# Sheet1.net
KiCad netlist of a schematic drawn in Altium Designer
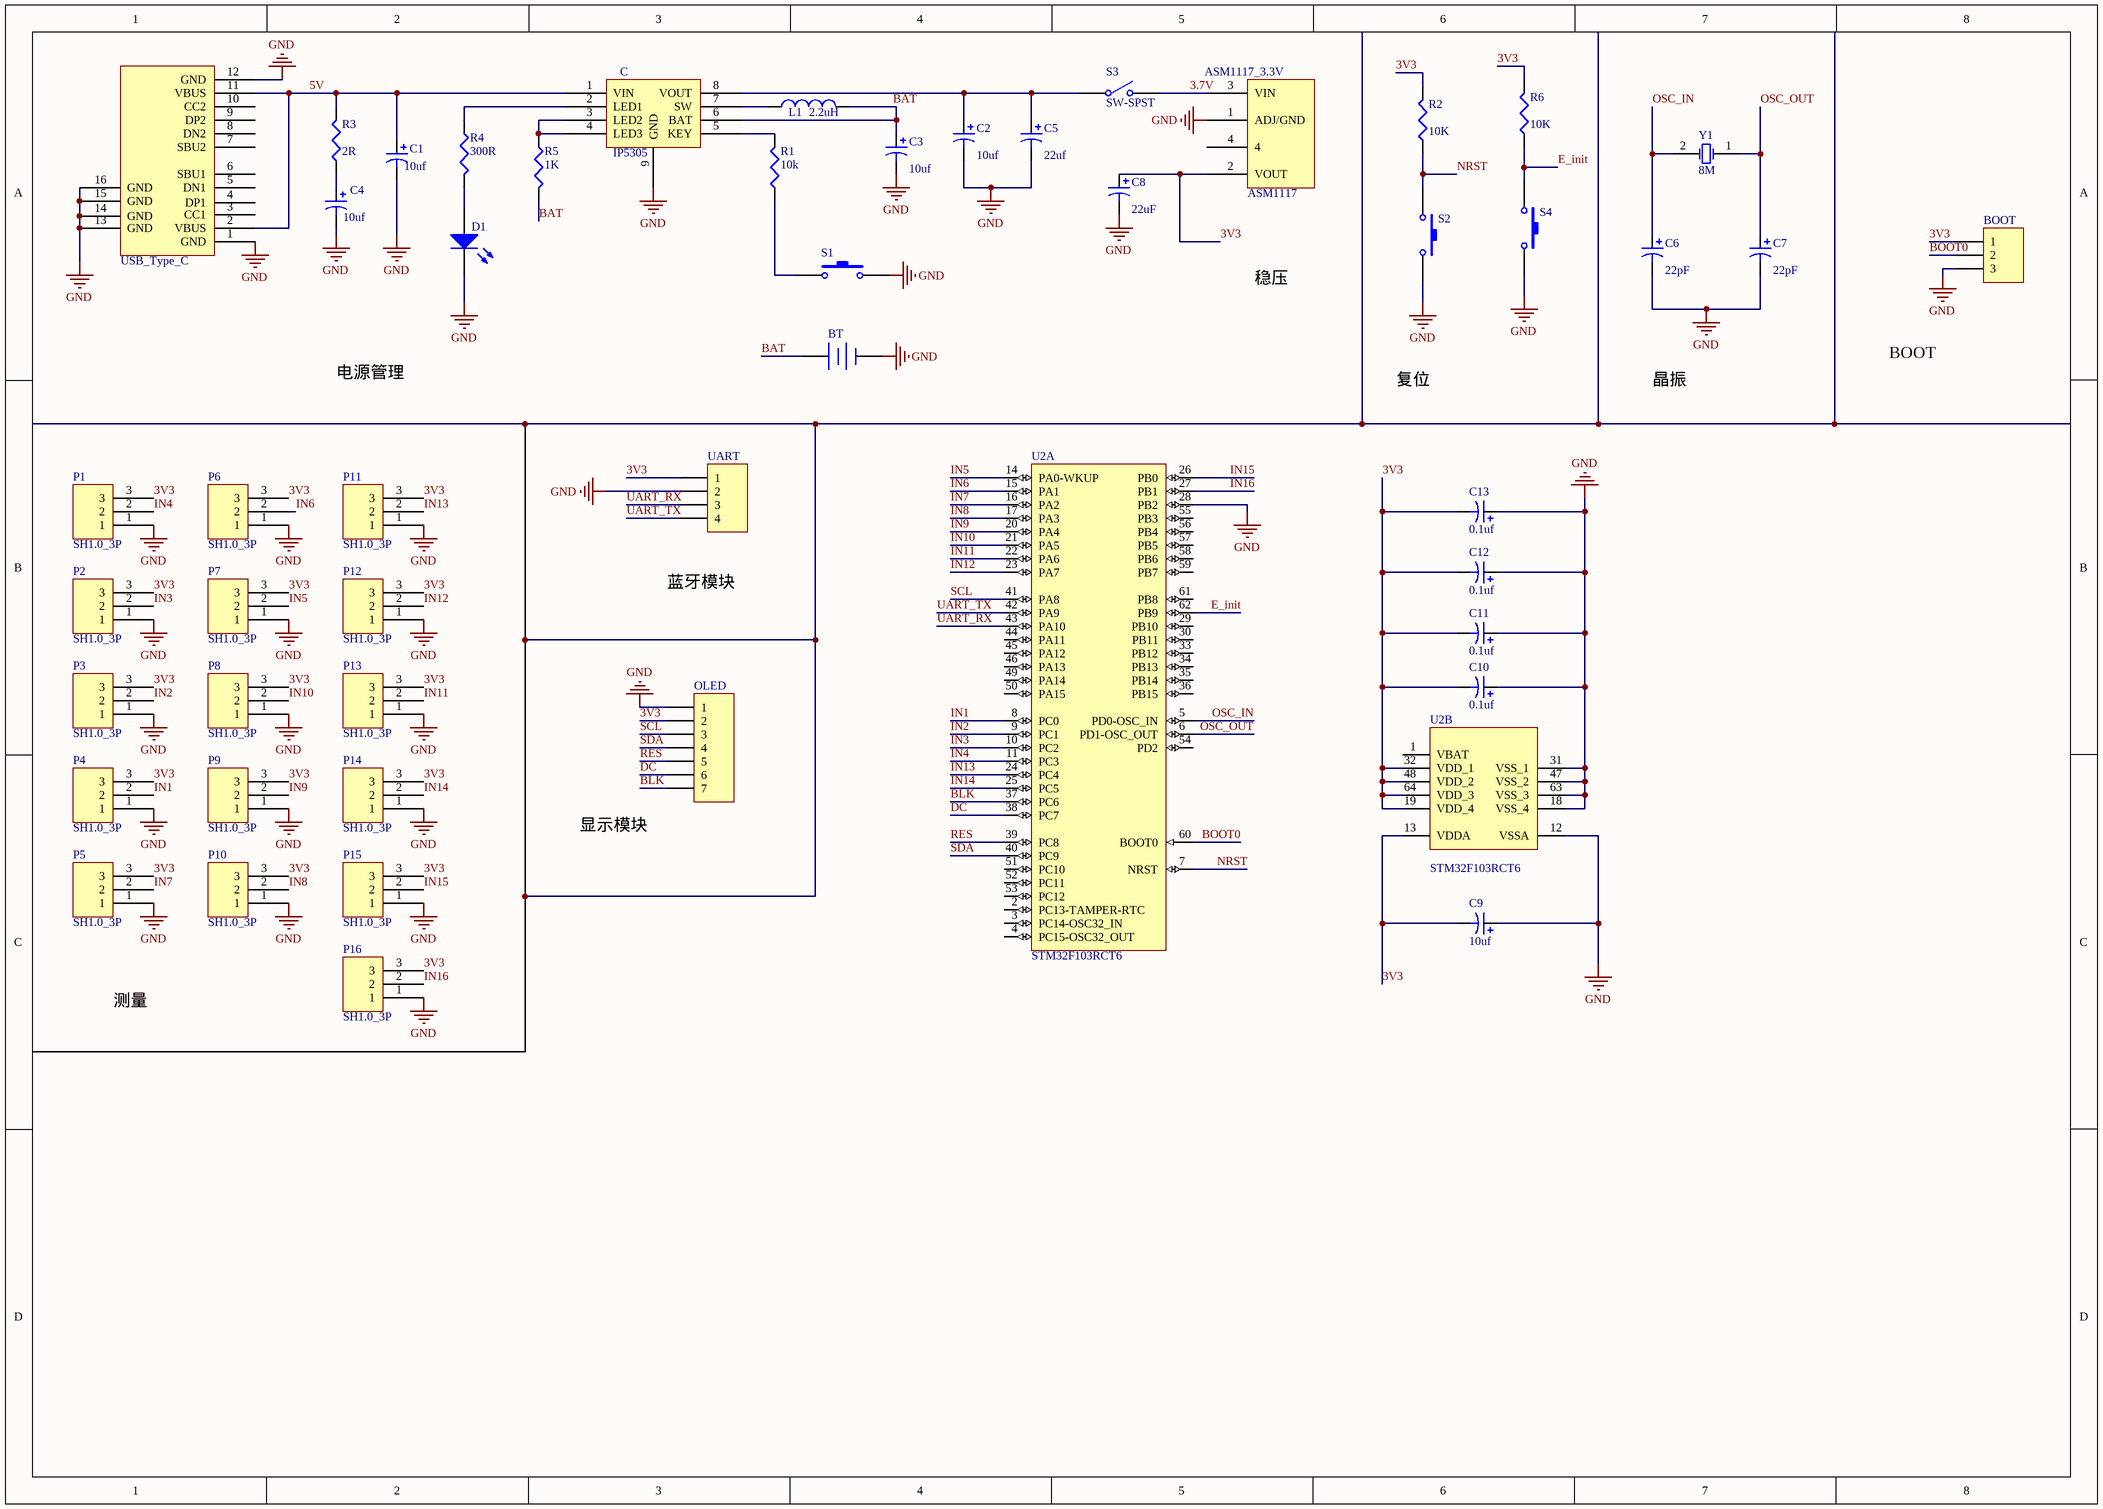
[diagram p0: Sheet1.SchDoc]

(export (version "E")
  (design (tool "Eeschema 10.0.6"))
  (components
    (comp (ref "*")
      (value "USB_Type_C")
      (footprint "USB_Type_C")
      (libsource (lib "Schlib1") (part "USB_Type_C"))
    )
    (comp (ref "ASM1117")
      (value "ASM1117_3.3V")
      (footprint "SOT223_N")
      (libsource (lib "Schlib1") (part "ASM1117_3.3V"))
    )
    (comp (ref "BOOT")
      (value "Header 3")
      (footprint "HDR1X3")
      (description "Header, 3-Pin")
      (fields (field (name "PUBLISHER") "Altium Limited"))
      (libsource (lib "Miscellaneous Connectors") (part "Header 3"))
    )
    (comp (ref "BT")
      (value "Battery")
      (footprint "BAT-2")
      (description "Multicell Battery")
      (fields (field (name "PUBLISHER") "Altium Limited"))
      (libsource (lib "Miscellaneous Devices") (part "Battery"))
    )
    (comp (ref "C") (value "IP5305") (footprint "SOP8_1") (libsource (lib "Schlib1") (part "IP5305")))
    (comp (ref "C1")
      (value "10uf")
      (footprint "J1-0603")
      (description "Polarized Capacitor (Surface Mount)")
      (fields (field (name "Comment") "Cap Pol3") (field (name "PUBLISHER") "Altium Limited"))
      (libsource (lib "Miscellaneous Devices") (part "Cap Pol3"))
    )
    (comp (ref "C2")
      (value "10uf")
      (footprint "J1-0603")
      (description "Polarized Capacitor (Surface Mount)")
      (fields (field (name "Comment") "Cap Pol3") (field (name "PUBLISHER") "Altium Limited"))
      (libsource (lib "Miscellaneous Devices") (part "Cap Pol3"))
    )
    (comp (ref "C3")
      (value "10uf")
      (footprint "J1-0603")
      (description "Polarized Capacitor (Surface Mount)")
      (fields (field (name "Comment") "Cap Pol3") (field (name "PUBLISHER") "Altium Limited"))
      (libsource (lib "Miscellaneous Devices") (part "Cap Pol3"))
    )
    (comp (ref "C4")
      (value "10uf")
      (footprint "J1-0603")
      (description "Polarized Capacitor (Surface Mount)")
      (fields (field (name "Comment") "Cap Pol3") (field (name "PUBLISHER") "Altium Limited"))
      (libsource (lib "Miscellaneous Devices") (part "Cap Pol3"))
    )
    (comp (ref "C5")
      (value "22uf")
      (footprint "J1-0603")
      (description "Polarized Capacitor (Surface Mount)")
      (fields (field (name "Comment") "Cap Pol3") (field (name "PUBLISHER") "Altium Limited"))
      (libsource (lib "Miscellaneous Devices") (part "Cap Pol3"))
    )
    (comp (ref "C6")
      (value "22pF")
      (footprint "J1-0603")
      (description "Polarized Capacitor (Surface Mount)")
      (fields (field (name "Comment") "Cap Pol3") (field (name "PUBLISHER") "Altium Limited"))
      (libsource (lib "Miscellaneous Devices") (part "Cap Pol3"))
    )
    (comp (ref "C7")
      (value "22pF")
      (footprint "J1-0603")
      (description "Polarized Capacitor (Surface Mount)")
      (fields (field (name "Comment") "Cap Pol3") (field (name "PUBLISHER") "Altium Limited"))
      (libsource (lib "Miscellaneous Devices") (part "Cap Pol3"))
    )
    (comp (ref "C8")
      (value "22uF")
      (footprint "J1-0603")
      (description "Polarized Capacitor (Surface Mount)")
      (fields (field (name "Comment") "Cap Pol3") (field (name "PUBLISHER") "Altium Limited"))
      (libsource (lib "Miscellaneous Devices") (part "Cap Pol3"))
    )
    (comp (ref "C9")
      (value "10uf")
      (footprint "J1-0603")
      (description "Polarized Capacitor (Surface Mount)")
      (fields (field (name "Comment") "Cap Pol3") (field (name "PUBLISHER") "Altium Limited"))
      (libsource (lib "Miscellaneous Devices") (part "Cap Pol3"))
    )
    (comp (ref "C10")
      (value "0.1uf")
      (footprint "J1-0603")
      (description "Polarized Capacitor (Surface Mount)")
      (fields (field (name "Comment") "Cap Pol3") (field (name "PUBLISHER") "Altium Limited"))
      (libsource (lib "Miscellaneous Devices") (part "Cap Pol3"))
    )
    (comp (ref "C11")
      (value "0.1uf")
      (footprint "J1-0603")
      (description "Polarized Capacitor (Surface Mount)")
      (fields (field (name "Comment") "Cap Pol3") (field (name "PUBLISHER") "Altium Limited"))
      (libsource (lib "Miscellaneous Devices") (part "Cap Pol3"))
    )
    (comp (ref "C12")
      (value "0.1uf")
      (footprint "J1-0603")
      (description "Polarized Capacitor (Surface Mount)")
      (fields (field (name "Comment") "Cap Pol3") (field (name "PUBLISHER") "Altium Limited"))
      (libsource (lib "Miscellaneous Devices") (part "Cap Pol3"))
    )
    (comp (ref "C13")
      (value "0.1uf")
      (footprint "J1-0603")
      (description "Polarized Capacitor (Surface Mount)")
      (fields (field (name "Comment") "Cap Pol3") (field (name "PUBLISHER") "Altium Limited"))
      (libsource (lib "Miscellaneous Devices") (part "Cap Pol3"))
    )
    (comp (ref "D1")
      (value "LED2")
      (footprint "J1-0603")
      (description "Typical RED, GREEN, YELLOW, AMBER GaAs LED")
      (fields (field (name "PUBLISHER") "Altium Limited"))
      (libsource (lib "Miscellaneous Devices") (part "LED2"))
    )
    (comp (ref "L1")
      (value "2.2uH")
      (footprint "CD43")
      (description "Inductor")
      (fields (field (name "PUBLISHER") "Altium Limited"))
      (libsource (lib "Miscellaneous Devices") (part "Inductor"))
    )
    (comp (ref "OLED")
      (value "MHDR1X7")
      (footprint "HDR1X7")
      (description "Header, 7-Pin")
      (fields (field (name "PUBLISHER") "Altium Limited"))
      (libsource (lib "Miscellaneous Connectors") (part "MHDR1X7"))
    )
    (comp (ref "P1") (value "SH1.0_3P") (footprint "SH1_3P_2") (libsource (lib "Schlib1") (part "SH1.0_3P")))
    (comp (ref "P2") (value "SH1.0_3P") (footprint "SH1_3P_2") (libsource (lib "Schlib1") (part "SH1.0_3P")))
    (comp (ref "P3") (value "SH1.0_3P") (footprint "SH1_3P_2") (libsource (lib "Schlib1") (part "SH1.0_3P")))
    (comp (ref "P4") (value "SH1.0_3P") (footprint "SH1_3P_2") (libsource (lib "Schlib1") (part "SH1.0_3P")))
    (comp (ref "P5") (value "SH1.0_3P") (footprint "SH1_3P_2") (libsource (lib "Schlib1") (part "SH1.0_3P")))
    (comp (ref "P6") (value "SH1.0_3P") (footprint "SH1_3P_2") (libsource (lib "Schlib1") (part "SH1.0_3P")))
    (comp (ref "P7") (value "SH1.0_3P") (footprint "SH1_3P_2") (libsource (lib "Schlib1") (part "SH1.0_3P")))
    (comp (ref "P8") (value "SH1.0_3P") (footprint "SH1_3P_2") (libsource (lib "Schlib1") (part "SH1.0_3P")))
    (comp (ref "P9") (value "SH1.0_3P") (footprint "SH1_3P_2") (libsource (lib "Schlib1") (part "SH1.0_3P")))
    (comp (ref "P10") (value "SH1.0_3P") (footprint "SH1_3P_2") (libsource (lib "Schlib1") (part "SH1.0_3P")))
    (comp (ref "P11") (value "SH1.0_3P") (footprint "SH1_3P_2") (libsource (lib "Schlib1") (part "SH1.0_3P")))
    (comp (ref "P12") (value "SH1.0_3P") (footprint "SH1_3P_2") (libsource (lib "Schlib1") (part "SH1.0_3P")))
    (comp (ref "P13") (value "SH1.0_3P") (footprint "SH1_3P_2") (libsource (lib "Schlib1") (part "SH1.0_3P")))
    (comp (ref "P14") (value "SH1.0_3P") (footprint "SH1_3P_2") (libsource (lib "Schlib1") (part "SH1.0_3P")))
    (comp (ref "P15") (value "SH1.0_3P") (footprint "SH1_3P_2") (libsource (lib "Schlib1") (part "SH1.0_3P")))
    (comp (ref "P16") (value "SH1.0_3P") (footprint "SH1_3P_2") (libsource (lib "Schlib1") (part "SH1.0_3P")))
    (comp (ref "R1")
      (value "10k")
      (footprint "J1-0603")
      (description "Resistor")
      (fields (field (name "Comment") "Res3") (field (name "PUBLISHER") "Altium Limited"))
      (libsource (lib "Miscellaneous Devices") (part "Res3"))
    )
    (comp (ref "R2")
      (value "10K")
      (footprint "J1-0603")
      (description "Resistor")
      (fields (field (name "Comment") "Res3") (field (name "PUBLISHER") "Altium Limited"))
      (libsource (lib "Miscellaneous Devices") (part "Res3"))
    )
    (comp (ref "R3")
      (value "2R")
      (footprint "J1-0603")
      (description "Resistor")
      (fields (field (name "Comment") "Res3") (field (name "PUBLISHER") "Altium Limited"))
      (libsource (lib "Miscellaneous Devices") (part "Res3"))
    )
    (comp (ref "R4")
      (value "300R")
      (footprint "J1-0603")
      (description "Resistor")
      (fields (field (name "Comment") "Res3") (field (name "PUBLISHER") "Altium Limited"))
      (libsource (lib "Miscellaneous Devices") (part "Res3"))
    )
    (comp (ref "R5")
      (value "1K")
      (footprint "J1-0603")
      (description "Resistor")
      (fields (field (name "Comment") "Res3") (field (name "PUBLISHER") "Altium Limited"))
      (libsource (lib "Miscellaneous Devices") (part "Res3"))
    )
    (comp (ref "R6")
      (value "10K")
      (footprint "J1-0603")
      (description "Resistor")
      (fields (field (name "Comment") "Res3") (field (name "PUBLISHER") "Altium Limited"))
      (libsource (lib "Miscellaneous Devices") (part "Res3"))
    )
    (comp (ref "S1")
      (value "SW-PB")
      (footprint "SW_DP_1")
      (description "Switch")
      (fields (field (name "PUBLISHER") "Altium Limited"))
      (libsource (lib "Miscellaneous Devices") (part "SW-PB"))
    )
    (comp (ref "S2")
      (value "SW-PB")
      (footprint "SW_DP_1")
      (description "Switch")
      (fields (field (name "PUBLISHER") "Altium Limited"))
      (libsource (lib "Miscellaneous Devices") (part "SW-PB"))
    )
    (comp (ref "S3")
      (value "SW-SPST")
      (footprint "SW_s1")
      (description "Single-Pole, Single-Throw Switch")
      (fields (field (name "PUBLISHER") "Altium Limited"))
      (libsource (lib "Miscellaneous Devices") (part "SW-SPST"))
    )
    (comp (ref "S4")
      (value "SW-PB")
      (footprint "SW_DP_1")
      (description "Switch")
      (fields (field (name "PUBLISHER") "Altium Limited"))
      (libsource (lib "Miscellaneous Devices") (part "SW-PB"))
    )
    (comp (ref "U2")
      (value "STM32F103RCT6")
      (footprint "STM-LQFP64_N")
      (libsource (lib "") (part "STM32F103RCT6_1"))
    )
    (comp (ref "UART")
      (value "Header 4")
      (footprint "HDR1X4")
      (description "Header, 4-Pin")
      (fields (field (name "PUBLISHER") "Altium Limited"))
      (libsource (lib "Miscellaneous Connectors") (part "Header 4"))
    )
    (comp (ref "Y1")
      (value "8M")
      (footprint "YXC_8M")
      (description "Crystal Oscillator")
      (fields (field (name "PUBLISHER") "Altium Limited"))
      (libsource (lib "Miscellaneous Devices") (part "XTAL"))
    )
  )
  (nets
    (net (code "1") (name "/3.7V") (class "Default")
      (node (ref "ASM1117") (pin "3") (pinfunction "VIN_3") (pintype "passive"))
      (node (ref "S3") (pin "2") (pinfunction "NO_2") (pintype "passive"))
    )
    (net (code "2") (name "/3V3") (class "Default")
      (node (ref "ASM1117") (pin "2") (pinfunction "VOUT_2") (pintype "passive"))
      (node (ref "BOOT") (pin "1") (pinfunction "1_1") (pintype "passive"))
      (node (ref "C10") (pin "2") (pinfunction "2_2") (pintype "passive"))
      (node (ref "C11") (pin "2") (pinfunction "2_2") (pintype "passive"))
      (node (ref "C12") (pin "2") (pinfunction "2_2") (pintype "passive"))
      (node (ref "C13") (pin "2") (pinfunction "2_2") (pintype "passive"))
      (node (ref "C8") (pin "1") (pinfunction "1_1") (pintype "passive"))
      (node (ref "C9") (pin "2") (pinfunction "2_2") (pintype "passive"))
      (node (ref "OLED") (pin "2") (pinfunction "2_2") (pintype "passive"))
      (node (ref "P1") (pin "3") (pinfunction "3_3") (pintype "passive"))
      (node (ref "P10") (pin "3") (pinfunction "3_3") (pintype "passive"))
      (node (ref "P11") (pin "3") (pinfunction "3_3") (pintype "passive"))
      (node (ref "P12") (pin "3") (pinfunction "3_3") (pintype "passive"))
      (node (ref "P13") (pin "3") (pinfunction "3_3") (pintype "passive"))
      (node (ref "P14") (pin "3") (pinfunction "3_3") (pintype "passive"))
      (node (ref "P15") (pin "3") (pinfunction "3_3") (pintype "passive"))
      (node (ref "P16") (pin "3") (pinfunction "3_3") (pintype "passive"))
      (node (ref "P2") (pin "3") (pinfunction "3_3") (pintype "passive"))
      (node (ref "P3") (pin "3") (pinfunction "3_3") (pintype "passive"))
      (node (ref "P4") (pin "3") (pinfunction "3_3") (pintype "passive"))
      (node (ref "P5") (pin "3") (pinfunction "3_3") (pintype "passive"))
      (node (ref "P6") (pin "3") (pinfunction "3_3") (pintype "passive"))
      (node (ref "P7") (pin "3") (pinfunction "3_3") (pintype "passive"))
      (node (ref "P8") (pin "3") (pinfunction "3_3") (pintype "passive"))
      (node (ref "P9") (pin "3") (pinfunction "3_3") (pintype "passive"))
      (node (ref "R2") (pin "2") (pinfunction "2_2") (pintype "passive"))
      (node (ref "R6") (pin "2") (pinfunction "2_2") (pintype "passive"))
      (node (ref "U2") (pin "13") (pinfunction "VDDA_13") (pintype "power_in"))
      (node (ref "U2") (pin "19") (pinfunction "VDD_4_19") (pintype "power_in"))
      (node (ref "U2") (pin "32") (pinfunction "VDD_1_32") (pintype "power_in"))
      (node (ref "U2") (pin "48") (pinfunction "VDD_2_48") (pintype "power_in"))
      (node (ref "U2") (pin "64") (pinfunction "VDD_3_64") (pintype "power_in"))
      (node (ref "UART") (pin "1") (pinfunction "1_1") (pintype "passive"))
    )
    (net (code "3") (name "/5V") (class "Default")
      (node (ref "*") (pin "11") (pinfunction "VBUS_11") (pintype "passive"))
      (node (ref "*") (pin "2") (pinfunction "VBUS_2") (pintype "passive"))
      (node (ref "C") (pin "1") (pinfunction "VIN_1") (pintype "passive"))
      (node (ref "C1") (pin "1") (pinfunction "1_1") (pintype "passive"))
      (node (ref "R3") (pin "2") (pinfunction "2_2") (pintype "passive"))
    )
    (net (code "4") (name "/BAT") (class "Default")
      (node (ref "BT") (pin "1") (pinfunction "+_1") (pintype "passive"))
      (node (ref "C") (pin "6") (pinfunction "BAT_6") (pintype "passive"))
      (node (ref "C3") (pin "1") (pinfunction "1_1") (pintype "passive"))
      (node (ref "L1") (pin "2") (pinfunction "2_2") (pintype "passive"))
      (node (ref "R5") (pin "2") (pinfunction "2_2") (pintype "passive"))
    )
    (net (code "5") (name "/BLK") (class "Default")
      (node (ref "OLED") (pin "7") (pinfunction "7_7") (pintype "passive"))
      (node (ref "U2") (pin "37") (pinfunction "PC6_37") (pintype "bidirectional"))
    )
    (net (code "6") (name "/BOOT0") (class "Default")
      (node (ref "BOOT") (pin "2") (pinfunction "2_2") (pintype "passive"))
      (node (ref "U2") (pin "60") (pinfunction "BOOT0_60") (pintype "input"))
    )
    (net (code "7") (name "/DC") (class "Default")
      (node (ref "OLED") (pin "6") (pinfunction "6_6") (pintype "passive"))
      (node (ref "U2") (pin "38") (pinfunction "PC7_38") (pintype "bidirectional"))
    )
    (net (code "8") (name "/E_init") (class "Default")
      (node (ref "R6") (pin "1") (pinfunction "1_1") (pintype "passive"))
      (node (ref "S4") (pin "1") (pinfunction "1_1") (pintype "passive"))
      (node (ref "U2") (pin "62") (pinfunction "PB9_62") (pintype "bidirectional"))
    )
    (net (code "9") (name "/IN1") (class "Default")
      (node (ref "P4") (pin "2") (pinfunction "2_2") (pintype "passive"))
      (node (ref "U2") (pin "8") (pinfunction "PC0_8") (pintype "bidirectional"))
    )
    (net (code "10") (name "/IN2") (class "Default")
      (node (ref "P3") (pin "2") (pinfunction "2_2") (pintype "passive"))
      (node (ref "U2") (pin "9") (pinfunction "PC1_9") (pintype "bidirectional"))
    )
    (net (code "11") (name "/IN3") (class "Default")
      (node (ref "P2") (pin "2") (pinfunction "2_2") (pintype "passive"))
      (node (ref "U2") (pin "10") (pinfunction "PC2_10") (pintype "bidirectional"))
    )
    (net (code "12") (name "/IN4") (class "Default")
      (node (ref "P1") (pin "2") (pinfunction "2_2") (pintype "passive"))
      (node (ref "U2") (pin "11") (pinfunction "PC3_11") (pintype "bidirectional"))
    )
    (net (code "13") (name "/IN5") (class "Default")
      (node (ref "P7") (pin "2") (pinfunction "2_2") (pintype "passive"))
      (node (ref "U2") (pin "14") (pinfunction "PA0-WKUP_14") (pintype "bidirectional"))
    )
    (net (code "14") (name "/IN6") (class "Default")
      (node (ref "P6") (pin "2") (pinfunction "2_2") (pintype "passive"))
      (node (ref "U2") (pin "15") (pinfunction "PA1_15") (pintype "bidirectional"))
    )
    (net (code "15") (name "/IN7") (class "Default")
      (node (ref "P5") (pin "2") (pinfunction "2_2") (pintype "passive"))
      (node (ref "U2") (pin "16") (pinfunction "PA2_16") (pintype "bidirectional"))
    )
    (net (code "16") (name "/IN8") (class "Default")
      (node (ref "P10") (pin "2") (pinfunction "2_2") (pintype "passive"))
      (node (ref "U2") (pin "17") (pinfunction "PA3_17") (pintype "bidirectional"))
    )
    (net (code "17") (name "/IN9") (class "Default")
      (node (ref "P9") (pin "2") (pinfunction "2_2") (pintype "passive"))
      (node (ref "U2") (pin "20") (pinfunction "PA4_20") (pintype "bidirectional"))
    )
    (net (code "18") (name "/IN10") (class "Default")
      (node (ref "P8") (pin "2") (pinfunction "2_2") (pintype "passive"))
      (node (ref "U2") (pin "21") (pinfunction "PA5_21") (pintype "bidirectional"))
    )
    (net (code "19") (name "/IN11") (class "Default")
      (node (ref "P13") (pin "2") (pinfunction "2_2") (pintype "passive"))
      (node (ref "U2") (pin "22") (pinfunction "PA6_22") (pintype "bidirectional"))
    )
    (net (code "20") (name "/IN12") (class "Default")
      (node (ref "P12") (pin "2") (pinfunction "2_2") (pintype "passive"))
      (node (ref "U2") (pin "23") (pinfunction "PA7_23") (pintype "bidirectional"))
    )
    (net (code "21") (name "/IN13") (class "Default")
      (node (ref "P11") (pin "2") (pinfunction "2_2") (pintype "passive"))
      (node (ref "U2") (pin "24") (pinfunction "PC4_24") (pintype "bidirectional"))
    )
    (net (code "22") (name "/IN14") (class "Default")
      (node (ref "P14") (pin "2") (pinfunction "2_2") (pintype "passive"))
      (node (ref "U2") (pin "25") (pinfunction "PC5_25") (pintype "bidirectional"))
    )
    (net (code "23") (name "/IN15") (class "Default")
      (node (ref "P15") (pin "2") (pinfunction "2_2") (pintype "passive"))
      (node (ref "U2") (pin "26") (pinfunction "PB0_26") (pintype "bidirectional"))
    )
    (net (code "24") (name "/IN16") (class "Default")
      (node (ref "P16") (pin "2") (pinfunction "2_2") (pintype "passive"))
      (node (ref "U2") (pin "27") (pinfunction "PB1_27") (pintype "bidirectional"))
    )
    (net (code "25") (name "/NRST") (class "Default")
      (node (ref "R2") (pin "1") (pinfunction "1_1") (pintype "passive"))
      (node (ref "S2") (pin "1") (pinfunction "1_1") (pintype "passive"))
      (node (ref "U2") (pin "7") (pinfunction "NRST_7") (pintype "bidirectional"))
    )
    (net (code "26") (name "/OSC_IN") (class "Default")
      (node (ref "C6") (pin "1") (pinfunction "1_1") (pintype "passive"))
      (node (ref "U2") (pin "5") (pinfunction "PD0-OSC_IN_5") (pintype "bidirectional"))
      (node (ref "Y1") (pin "2") (pinfunction "OSC2_2") (pintype "passive"))
    )
    (net (code "27") (name "/OSC_OUT") (class "Default")
      (node (ref "C7") (pin "1") (pinfunction "1_1") (pintype "passive"))
      (node (ref "U2") (pin "6") (pinfunction "PD1-OSC_OUT_6") (pintype "bidirectional"))
      (node (ref "Y1") (pin "1") (pinfunction "OSC1_1") (pintype "passive"))
    )
    (net (code "28") (name "/RES") (class "Default")
      (node (ref "OLED") (pin "5") (pinfunction "5_5") (pintype "passive"))
      (node (ref "U2") (pin "39") (pinfunction "PC8_39") (pintype "bidirectional"))
    )
    (net (code "29") (name "/SCL") (class "Default")
      (node (ref "OLED") (pin "3") (pinfunction "3_3") (pintype "passive"))
      (node (ref "U2") (pin "41") (pinfunction "PA8_41") (pintype "bidirectional"))
    )
    (net (code "30") (name "/SDA") (class "Default")
      (node (ref "OLED") (pin "4") (pinfunction "4_4") (pintype "passive"))
      (node (ref "U2") (pin "40") (pinfunction "PC9_40") (pintype "bidirectional"))
    )
    (net (code "31") (name "/UART_RX") (class "Default")
      (node (ref "U2") (pin "43") (pinfunction "PA10_43") (pintype "bidirectional"))
      (node (ref "UART") (pin "3") (pinfunction "3_3") (pintype "passive"))
    )
    (net (code "32") (name "/UART_TX") (class "Default")
      (node (ref "U2") (pin "42") (pinfunction "PA9_42") (pintype "bidirectional"))
      (node (ref "UART") (pin "4") (pinfunction "4_4") (pintype "passive"))
    )
    (net (code "33") (name "GND") (class "Default")
      (node (ref "*") (pin "1") (pinfunction "GND_1") (pintype "passive"))
      (node (ref "*") (pin "12") (pinfunction "GND_12") (pintype "passive"))
      (node (ref "*") (pin "13") (pinfunction "GND_13") (pintype "passive"))
      (node (ref "*") (pin "14") (pinfunction "GND_14") (pintype "passive"))
      (node (ref "*") (pin "15") (pinfunction "GND_15") (pintype "passive"))
      (node (ref "*") (pin "16") (pinfunction "GND_16") (pintype "passive"))
      (node (ref "ASM1117") (pin "1") (pinfunction "ADJ/GND_1") (pintype "passive"))
      (node (ref "BOOT") (pin "3") (pinfunction "3_3") (pintype "passive"))
      (node (ref "BT") (pin "2") (pinfunction "-_2") (pintype "passive"))
      (node (ref "C") (pin "9") (pinfunction "GND_9") (pintype "passive"))
      (node (ref "C1") (pin "2") (pinfunction "2_2") (pintype "passive"))
      (node (ref "C10") (pin "1") (pinfunction "1_1") (pintype "passive"))
      (node (ref "C11") (pin "1") (pinfunction "1_1") (pintype "passive"))
      (node (ref "C12") (pin "1") (pinfunction "1_1") (pintype "passive"))
      (node (ref "C13") (pin "1") (pinfunction "1_1") (pintype "passive"))
      (node (ref "C2") (pin "2") (pinfunction "2_2") (pintype "passive"))
      (node (ref "C3") (pin "2") (pinfunction "2_2") (pintype "passive"))
      (node (ref "C4") (pin "2") (pinfunction "2_2") (pintype "passive"))
      (node (ref "C5") (pin "2") (pinfunction "2_2") (pintype "passive"))
      (node (ref "C6") (pin "2") (pinfunction "2_2") (pintype "passive"))
      (node (ref "C7") (pin "2") (pinfunction "2_2") (pintype "passive"))
      (node (ref "C8") (pin "2") (pinfunction "2_2") (pintype "passive"))
      (node (ref "C9") (pin "1") (pinfunction "1_1") (pintype "passive"))
      (node (ref "D1") (pin "2") (pinfunction "K_2") (pintype "passive"))
      (node (ref "OLED") (pin "1") (pinfunction "1_1") (pintype "passive"))
      (node (ref "P1") (pin "1") (pinfunction "1_1") (pintype "passive"))
      (node (ref "P10") (pin "1") (pinfunction "1_1") (pintype "passive"))
      (node (ref "P11") (pin "1") (pinfunction "1_1") (pintype "passive"))
      (node (ref "P12") (pin "1") (pinfunction "1_1") (pintype "passive"))
      (node (ref "P13") (pin "1") (pinfunction "1_1") (pintype "passive"))
      (node (ref "P14") (pin "1") (pinfunction "1_1") (pintype "passive"))
      (node (ref "P15") (pin "1") (pinfunction "1_1") (pintype "passive"))
      (node (ref "P16") (pin "1") (pinfunction "1_1") (pintype "passive"))
      (node (ref "P2") (pin "1") (pinfunction "1_1") (pintype "passive"))
      (node (ref "P3") (pin "1") (pinfunction "1_1") (pintype "passive"))
      (node (ref "P4") (pin "1") (pinfunction "1_1") (pintype "passive"))
      (node (ref "P5") (pin "1") (pinfunction "1_1") (pintype "passive"))
      (node (ref "P6") (pin "1") (pinfunction "1_1") (pintype "passive"))
      (node (ref "P7") (pin "1") (pinfunction "1_1") (pintype "passive"))
      (node (ref "P8") (pin "1") (pinfunction "1_1") (pintype "passive"))
      (node (ref "P9") (pin "1") (pinfunction "1_1") (pintype "passive"))
      (node (ref "S1") (pin "2") (pinfunction "2_2") (pintype "passive"))
      (node (ref "S2") (pin "2") (pinfunction "2_2") (pintype "passive"))
      (node (ref "S4") (pin "2") (pinfunction "2_2") (pintype "passive"))
      (node (ref "U2") (pin "12") (pinfunction "VSSA_12") (pintype "power_in"))
      (node (ref "U2") (pin "18") (pinfunction "VSS_4_18") (pintype "power_in"))
      (node (ref "U2") (pin "28") (pinfunction "PB2_28") (pintype "bidirectional"))
      (node (ref "U2") (pin "31") (pinfunction "VSS_1_31") (pintype "power_in"))
      (node (ref "U2") (pin "47") (pinfunction "VSS_2_47") (pintype "power_in"))
      (node (ref "U2") (pin "63") (pinfunction "VSS_3_63") (pintype "power_in"))
      (node (ref "UART") (pin "2") (pinfunction "2_2") (pintype "passive"))
    )
    (net (code "34") (name "Net-(C-KEY)") (class "Default")
      (node (ref "C") (pin "5") (pinfunction "KEY_5") (pintype "passive"))
      (node (ref "R1") (pin "2") (pinfunction "2_2") (pintype "passive"))
    )
    (net (code "35") (name "Net-(C-LED1)") (class "Default")
      (node (ref "C") (pin "2") (pinfunction "LED1_2") (pintype "passive"))
      (node (ref "R4") (pin "1") (pinfunction "1_1") (pintype "passive"))
    )
    (net (code "36") (name "Net-(C-LED2)") (class "Default")
      (node (ref "C") (pin "3") (pinfunction "LED2_3") (pintype "passive"))
      (node (ref "C") (pin "4") (pinfunction "LED3_4") (pintype "passive"))
      (node (ref "R5") (pin "1") (pinfunction "1_1") (pintype "passive"))
    )
    (net (code "37") (name "Net-(C-SW)") (class "Default")
      (node (ref "C") (pin "7") (pinfunction "SW_7") (pintype "passive"))
      (node (ref "L1") (pin "1") (pinfunction "1_1") (pintype "passive"))
    )
    (net (code "38") (name "Net-(C-VOUT)") (class "Default")
      (node (ref "C") (pin "8") (pinfunction "VOUT_8") (pintype "passive"))
      (node (ref "C2") (pin "1") (pinfunction "1_1") (pintype "passive"))
      (node (ref "C5") (pin "1") (pinfunction "1_1") (pintype "passive"))
      (node (ref "S3") (pin "1") (pinfunction "COMMON_1") (pintype "passive"))
    )
    (net (code "39") (name "Net-(C4-Pad1)") (class "Default")
      (node (ref "C4") (pin "1") (pinfunction "1_1") (pintype "passive"))
      (node (ref "R3") (pin "1") (pinfunction "1_1") (pintype "passive"))
    )
    (net (code "40") (name "Net-(D1-A)") (class "Default")
      (node (ref "D1") (pin "1") (pinfunction "A_1") (pintype "passive"))
      (node (ref "R4") (pin "2") (pinfunction "2_2") (pintype "passive"))
    )
    (net (code "41") (name "Net-(R1-Pad1)") (class "Default")
      (node (ref "R1") (pin "1") (pinfunction "1_1") (pintype "passive"))
      (node (ref "S1") (pin "1") (pinfunction "1_1") (pintype "passive"))
    )
    (net (code "42") (name "unconnected-(*-CC1-Pad3)") (class "Default")
      (node (ref "*") (pin "3") (pinfunction "CC1_3") (pintype "passive"))
    )
    (net (code "43") (name "unconnected-(*-CC2-Pad10)") (class "Default")
      (node (ref "*") (pin "10") (pinfunction "CC2_10") (pintype "passive"))
    )
    (net (code "44") (name "unconnected-(*-DN1-Pad5)") (class "Default")
      (node (ref "*") (pin "5") (pinfunction "DN1_5") (pintype "passive"))
    )
    (net (code "45") (name "unconnected-(*-DN2-Pad8)") (class "Default")
      (node (ref "*") (pin "8") (pinfunction "DN2_8") (pintype "passive"))
    )
    (net (code "46") (name "unconnected-(*-DP1-Pad4)") (class "Default")
      (node (ref "*") (pin "4") (pinfunction "DP1_4") (pintype "passive"))
    )
    (net (code "47") (name "unconnected-(*-DP2-Pad9)") (class "Default")
      (node (ref "*") (pin "9") (pinfunction "DP2_9") (pintype "passive"))
    )
    (net (code "48") (name "unconnected-(*-SBU1-Pad6)") (class "Default")
      (node (ref "*") (pin "6") (pinfunction "SBU1_6") (pintype "passive"))
    )
    (net (code "49") (name "unconnected-(*-SBU2-Pad7)") (class "Default")
      (node (ref "*") (pin "7") (pinfunction "SBU2_7") (pintype "passive"))
    )
    (net (code "50") (name "unconnected-(ASM1117-Pad4)") (class "Default")
      (node (ref "ASM1117") (pin "4") (pinfunction "4_4") (pintype "passive"))
    )
    (net (code "51") (name "unconnected-(U2A-PA11-Pad44)") (class "Default")
      (node (ref "U2") (pin "44") (pinfunction "PA11_44") (pintype "bidirectional"))
    )
    (net (code "52") (name "unconnected-(U2A-PA12-Pad45)") (class "Default")
      (node (ref "U2") (pin "45") (pinfunction "PA12_45") (pintype "bidirectional"))
    )
    (net (code "53") (name "unconnected-(U2A-PA13-Pad46)") (class "Default")
      (node (ref "U2") (pin "46") (pinfunction "PA13_46") (pintype "bidirectional"))
    )
    (net (code "54") (name "unconnected-(U2A-PA14-Pad49)") (class "Default")
      (node (ref "U2") (pin "49") (pinfunction "PA14_49") (pintype "bidirectional"))
    )
    (net (code "55") (name "unconnected-(U2A-PA15-Pad50)") (class "Default")
      (node (ref "U2") (pin "50") (pinfunction "PA15_50") (pintype "bidirectional"))
    )
    (net (code "56") (name "unconnected-(U2A-PB3-Pad55)") (class "Default")
      (node (ref "U2") (pin "55") (pinfunction "PB3_55") (pintype "bidirectional"))
    )
    (net (code "57") (name "unconnected-(U2A-PB4-Pad56)") (class "Default")
      (node (ref "U2") (pin "56") (pinfunction "PB4_56") (pintype "bidirectional"))
    )
    (net (code "58") (name "unconnected-(U2A-PB5-Pad57)") (class "Default")
      (node (ref "U2") (pin "57") (pinfunction "PB5_57") (pintype "bidirectional"))
    )
    (net (code "59") (name "unconnected-(U2A-PB6-Pad58)") (class "Default")
      (node (ref "U2") (pin "58") (pinfunction "PB6_58") (pintype "bidirectional"))
    )
    (net (code "60") (name "unconnected-(U2A-PB7-Pad59)") (class "Default")
      (node (ref "U2") (pin "59") (pinfunction "PB7_59") (pintype "bidirectional"))
    )
    (net (code "61") (name "unconnected-(U2A-PB8-Pad61)") (class "Default")
      (node (ref "U2") (pin "61") (pinfunction "PB8_61") (pintype "bidirectional"))
    )
    (net (code "62") (name "unconnected-(U2A-PB10-Pad29)") (class "Default")
      (node (ref "U2") (pin "29") (pinfunction "PB10_29") (pintype "bidirectional"))
    )
    (net (code "63") (name "unconnected-(U2A-PB11-Pad30)") (class "Default")
      (node (ref "U2") (pin "30") (pinfunction "PB11_30") (pintype "bidirectional"))
    )
    (net (code "64") (name "unconnected-(U2A-PB12-Pad33)") (class "Default")
      (node (ref "U2") (pin "33") (pinfunction "PB12_33") (pintype "bidirectional"))
    )
    (net (code "65") (name "unconnected-(U2A-PB13-Pad34)") (class "Default")
      (node (ref "U2") (pin "34") (pinfunction "PB13_34") (pintype "bidirectional"))
    )
    (net (code "66") (name "unconnected-(U2A-PB14-Pad35)") (class "Default")
      (node (ref "U2") (pin "35") (pinfunction "PB14_35") (pintype "bidirectional"))
    )
    (net (code "67") (name "unconnected-(U2A-PB15-Pad36)") (class "Default")
      (node (ref "U2") (pin "36") (pinfunction "PB15_36") (pintype "bidirectional"))
    )
    (net (code "68") (name "unconnected-(U2A-PC10-Pad51)") (class "Default")
      (node (ref "U2") (pin "51") (pinfunction "PC10_51") (pintype "bidirectional"))
    )
    (net (code "69") (name "unconnected-(U2A-PC11-Pad52)") (class "Default")
      (node (ref "U2") (pin "52") (pinfunction "PC11_52") (pintype "bidirectional"))
    )
    (net (code "70") (name "unconnected-(U2A-PC12-Pad53)") (class "Default")
      (node (ref "U2") (pin "53") (pinfunction "PC12_53") (pintype "bidirectional"))
    )
    (net (code "71") (name "unconnected-(U2A-PC13-TAMPER-RTC-Pad2)") (class "Default")
      (node (ref "U2") (pin "2") (pinfunction "PC13-TAMPER-RTC_2") (pintype "bidirectional"))
    )
    (net (code "72") (name "unconnected-(U2A-PC14-OSC32_IN-Pad3)") (class "Default")
      (node (ref "U2") (pin "3") (pinfunction "PC14-OSC32_IN_3") (pintype "bidirectional"))
    )
    (net (code "73") (name "unconnected-(U2A-PC15-OSC32_OUT-Pad4)") (class "Default")
      (node (ref "U2") (pin "4") (pinfunction "PC15-OSC32_OUT_4") (pintype "bidirectional"))
    )
    (net (code "74") (name "unconnected-(U2A-PD2-Pad54)") (class "Default")
      (node (ref "U2") (pin "54") (pinfunction "PD2_54") (pintype "bidirectional"))
    )
    (net (code "75") (name "unconnected-(U2B-VBAT-Pad1)") (class "Default")
      (node (ref "U2") (pin "1") (pinfunction "VBAT_1") (pintype "power_in"))
    )
  )
)
